# led_kocka_shematic.net
KiCad netlist of a schematic drawn in EAGLE
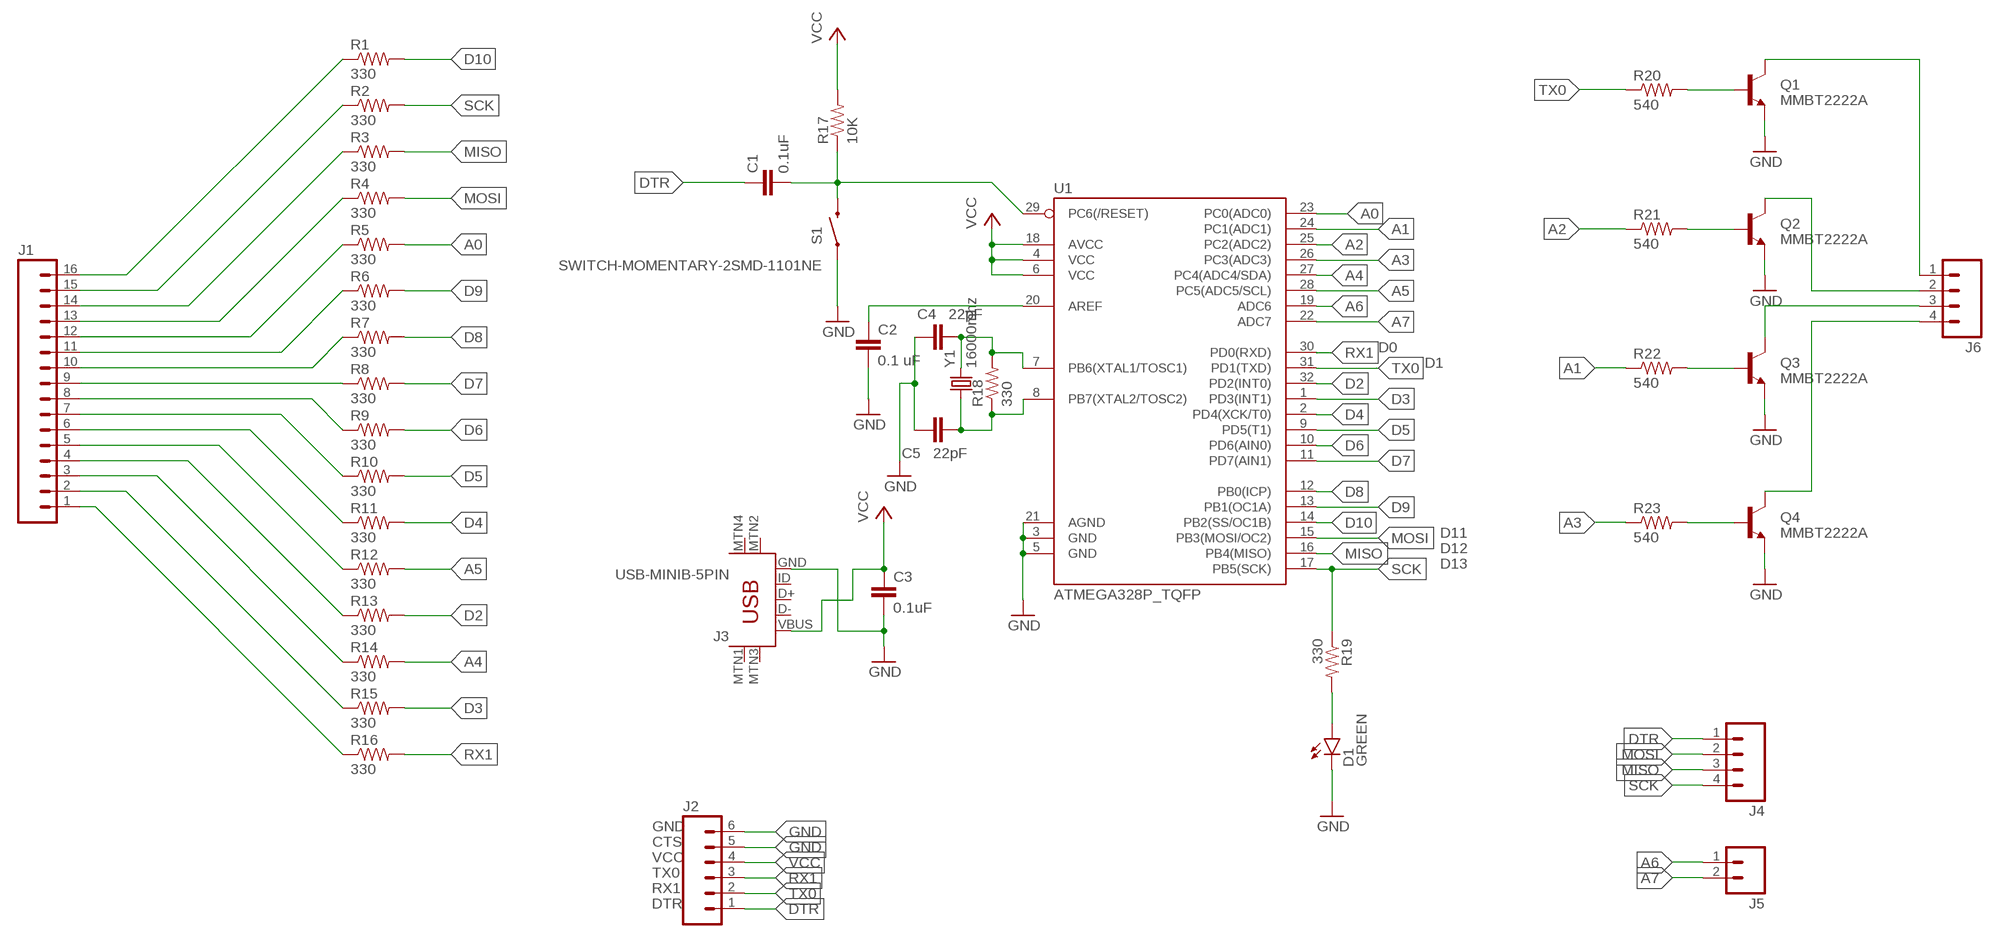
[diagram p0: schematic, sheet 1]

(export (version "E")
  (design (tool "Eeschema 10.0.6"))
  (components
    (comp (ref "C1")
      (value "0.1uF")
      (footprint "eagle-import:0805-CAP")
      (libsource (lib "eagle-import") (part "1UF-25V-10%(0805){dblquote}"))
    )
    (comp (ref "C2")
      (value "0.1 uF")
      (footprint "eagle-import:0805-CAP")
      (libsource (lib "eagle-import") (part "1UF-25V-10%(0805){dblquote}"))
    )
    (comp (ref "C3")
      (value "0.1uF")
      (footprint "eagle-import:0805-CAP")
      (libsource (lib "eagle-import") (part "1UF-25V-10%(0805){dblquote}"))
    )
    (comp (ref "C4")
      (value "22pF")
      (footprint "eagle-import:0805-CAP")
      (libsource (lib "eagle-import") (part "1UF-25V-10%(0805){dblquote}"))
    )
    (comp (ref "C5")
      (value "22pF")
      (footprint "eagle-import:0805-CAP")
      (libsource (lib "eagle-import") (part "1UF-25V-10%(0805){dblquote}"))
    )
    (comp (ref "D1")
      (value "GREEN")
      (footprint "eagle-import:LED-0603")
      (libsource (lib "eagle-import") (part "LED-GREEN0603"))
    )
    (comp (ref "J1")
      (value "M16LONGPADS")
      (footprint "eagle-import:1X16_LONGPADS")
      (libsource (lib "eagle-import") (part "M16LONGPADS"))
    )
    (comp (ref "J2")
      (value "M06LONGPADS")
      (footprint "eagle-import:1X06_LONGPADS")
      (libsource (lib "eagle-import") (part "M06LONGPADS"))
    )
    (comp (ref "J3")
      (value "USB-MINIB-5PIN")
      (footprint "eagle-import:USB-MINIB")
      (libsource (lib "eagle-import") (part "USB-MINIB-5PIN"))
    )
    (comp (ref "J4")
      (value "M04LONGPADS")
      (footprint "eagle-import:1X04_LONGPADS")
      (libsource (lib "eagle-import") (part "M04LONGPADS"))
    )
    (comp (ref "J5")
      (value "M02LOCK_LONGPADS")
      (footprint "eagle-import:1X02_LOCK_LONGPADS")
      (libsource (lib "eagle-import") (part "M02LOCK_LONGPADS"))
    )
    (comp (ref "J6")
      (value "M04LONGPADS")
      (footprint "eagle-import:1X04_LONGPADS")
      (libsource (lib "eagle-import") (part "M04LONGPADS"))
    )
    (comp (ref "Q1")
      (value "MMBT2222A")
      (footprint "eagle-import:SOT23-3")
      (libsource (lib "eagle-import") (part "TRANSISTOR_NPNMMBT2222A"))
    )
    (comp (ref "Q2")
      (value "MMBT2222A")
      (footprint "eagle-import:SOT23-3")
      (libsource (lib "eagle-import") (part "TRANSISTOR_NPNMMBT2222A"))
    )
    (comp (ref "Q3")
      (value "MMBT2222A")
      (footprint "eagle-import:SOT23-3")
      (libsource (lib "eagle-import") (part "TRANSISTOR_NPNMMBT2222A"))
    )
    (comp (ref "Q4")
      (value "MMBT2222A")
      (footprint "eagle-import:SOT23-3")
      (libsource (lib "eagle-import") (part "TRANSISTOR_NPNMMBT2222A"))
    )
    (comp (ref "R1")
      (value "330")
      (footprint "eagle-import:R0805")
      (libsource (lib "eagle-import") (part "R-US_R0805"))
    )
    (comp (ref "R2")
      (value "330")
      (footprint "eagle-import:R0805")
      (libsource (lib "eagle-import") (part "R-US_R0805"))
    )
    (comp (ref "R3")
      (value "330")
      (footprint "eagle-import:R0805")
      (libsource (lib "eagle-import") (part "R-US_R0805"))
    )
    (comp (ref "R4")
      (value "330")
      (footprint "eagle-import:R0805")
      (libsource (lib "eagle-import") (part "R-US_R0805"))
    )
    (comp (ref "R5")
      (value "330")
      (footprint "eagle-import:R0805")
      (libsource (lib "eagle-import") (part "R-US_R0805"))
    )
    (comp (ref "R6")
      (value "330")
      (footprint "eagle-import:R0805")
      (libsource (lib "eagle-import") (part "R-US_R0805"))
    )
    (comp (ref "R7")
      (value "330")
      (footprint "eagle-import:R0805")
      (libsource (lib "eagle-import") (part "R-US_R0805"))
    )
    (comp (ref "R8")
      (value "330")
      (footprint "eagle-import:R0805")
      (libsource (lib "eagle-import") (part "R-US_R0805"))
    )
    (comp (ref "R9")
      (value "330")
      (footprint "eagle-import:R0805")
      (libsource (lib "eagle-import") (part "R-US_R0805"))
    )
    (comp (ref "R10")
      (value "330")
      (footprint "eagle-import:R0805")
      (libsource (lib "eagle-import") (part "R-US_R0805"))
    )
    (comp (ref "R11")
      (value "330")
      (footprint "eagle-import:R0805")
      (libsource (lib "eagle-import") (part "R-US_R0805"))
    )
    (comp (ref "R12")
      (value "330")
      (footprint "eagle-import:R0805")
      (libsource (lib "eagle-import") (part "R-US_R0805"))
    )
    (comp (ref "R13")
      (value "330")
      (footprint "eagle-import:R0805")
      (libsource (lib "eagle-import") (part "R-US_R0805"))
    )
    (comp (ref "R14")
      (value "330")
      (footprint "eagle-import:R0805")
      (libsource (lib "eagle-import") (part "R-US_R0805"))
    )
    (comp (ref "R15")
      (value "330")
      (footprint "eagle-import:R0805")
      (libsource (lib "eagle-import") (part "R-US_R0805"))
    )
    (comp (ref "R16")
      (value "330")
      (footprint "eagle-import:R0805")
      (libsource (lib "eagle-import") (part "R-US_R0805"))
    )
    (comp (ref "R17")
      (value "10K")
      (footprint "eagle-import:R0805")
      (libsource (lib "eagle-import") (part "R-US_R0805"))
    )
    (comp (ref "R18")
      (value "330")
      (footprint "eagle-import:R0805")
      (libsource (lib "eagle-import") (part "R-US_R0805"))
    )
    (comp (ref "R19")
      (value "330")
      (footprint "eagle-import:R0805")
      (libsource (lib "eagle-import") (part "R-US_R0805"))
    )
    (comp (ref "R20")
      (value "540")
      (footprint "eagle-import:R0805")
      (libsource (lib "eagle-import") (part "R-US_R0805"))
    )
    (comp (ref "R21")
      (value "540")
      (footprint "eagle-import:R0805")
      (libsource (lib "eagle-import") (part "R-US_R0805"))
    )
    (comp (ref "R22")
      (value "540")
      (footprint "eagle-import:R0805")
      (libsource (lib "eagle-import") (part "R-US_R0805"))
    )
    (comp (ref "R23")
      (value "540")
      (footprint "eagle-import:R0805")
      (libsource (lib "eagle-import") (part "R-US_R0805"))
    )
    (comp (ref "S1")
      (value "SWITCH-MOMENTARY-2SMD-1101NE")
      (footprint "eagle-import:TACTILE-SWITCH-1101NE")
      (libsource (lib "eagle-import") (part "SWITCH-MOMENTARY-2SMD-1101NE"))
    )
    (comp (ref "U1")
      (value "ATMEGA328P_TQFP")
      (footprint "eagle-import:TQFP32-08")
      (libsource (lib "eagle-import") (part "ATMEGA328P_TQFP"))
    )
    (comp (ref "Y1")
      (value "16000mhz")
      (footprint "eagle-import:HC49UP")
      (libsource (lib "eagle-import") (part "CRYSTALSMD"))
    )
  )
  (nets
    (net (code "1") (name "A0") (class "Default")
      (node (ref "R5") (pin "2") (pinfunction "2_2") (pintype "passive"))
      (node (ref "U1") (pin "23") (pinfunction "PC0(ADC0)_23") (pintype "bidirectional"))
    )
    (net (code "2") (name "A1") (class "Default")
      (node (ref "R22") (pin "1") (pinfunction "1_1") (pintype "passive"))
      (node (ref "U1") (pin "24") (pinfunction "PC1(ADC1)_24") (pintype "bidirectional"))
    )
    (net (code "3") (name "A2") (class "Default")
      (node (ref "R21") (pin "1") (pinfunction "1_1") (pintype "passive"))
      (node (ref "U1") (pin "25") (pinfunction "PC2(ADC2)_25") (pintype "bidirectional"))
    )
    (net (code "4") (name "A3") (class "Default")
      (node (ref "R23") (pin "1") (pinfunction "1_1") (pintype "passive"))
      (node (ref "U1") (pin "26") (pinfunction "PC3(ADC3)_26") (pintype "bidirectional"))
    )
    (net (code "5") (name "A4") (class "Default")
      (node (ref "R14") (pin "2") (pinfunction "2_2") (pintype "passive"))
      (node (ref "U1") (pin "27") (pinfunction "PC4(ADC4/SDA)_27") (pintype "bidirectional"))
    )
    (net (code "6") (name "A5") (class "Default")
      (node (ref "R12") (pin "2") (pinfunction "2_2") (pintype "passive"))
      (node (ref "U1") (pin "28") (pinfunction "PC5(ADC5/SCL)_28") (pintype "bidirectional"))
    )
    (net (code "7") (name "A6") (class "Default")
      (node (ref "J5") (pin "1") (pinfunction "1_1") (pintype "passive"))
      (node (ref "U1") (pin "19") (pinfunction "ADC6_19") (pintype "bidirectional"))
    )
    (net (code "8") (name "A7") (class "Default")
      (node (ref "J5") (pin "2") (pinfunction "2_2") (pintype "passive"))
      (node (ref "U1") (pin "22") (pinfunction "ADC7_22") (pintype "bidirectional"))
    )
    (net (code "9") (name "D2") (class "Default")
      (node (ref "R13") (pin "2") (pinfunction "2_2") (pintype "passive"))
      (node (ref "U1") (pin "32") (pinfunction "PD2(INT0)_32") (pintype "bidirectional"))
    )
    (net (code "10") (name "D3") (class "Default")
      (node (ref "R15") (pin "2") (pinfunction "2_2") (pintype "passive"))
      (node (ref "U1") (pin "1") (pinfunction "PD3(INT1)_1") (pintype "bidirectional"))
    )
    (net (code "11") (name "D4") (class "Default")
      (node (ref "R11") (pin "2") (pinfunction "2_2") (pintype "passive"))
      (node (ref "U1") (pin "2") (pinfunction "PD4(XCK/T0)_2") (pintype "bidirectional"))
    )
    (net (code "12") (name "D5") (class "Default")
      (node (ref "R10") (pin "2") (pinfunction "2_2") (pintype "passive"))
      (node (ref "U1") (pin "9") (pinfunction "PD5(T1)_9") (pintype "bidirectional"))
    )
    (net (code "13") (name "D6") (class "Default")
      (node (ref "R9") (pin "2") (pinfunction "2_2") (pintype "passive"))
      (node (ref "U1") (pin "10") (pinfunction "PD6(AIN0)_10") (pintype "bidirectional"))
    )
    (net (code "14") (name "D7") (class "Default")
      (node (ref "R8") (pin "2") (pinfunction "2_2") (pintype "passive"))
      (node (ref "U1") (pin "11") (pinfunction "PD7(AIN1)_11") (pintype "bidirectional"))
    )
    (net (code "15") (name "D8") (class "Default")
      (node (ref "R7") (pin "2") (pinfunction "2_2") (pintype "passive"))
      (node (ref "U1") (pin "12") (pinfunction "PB0(ICP)_12") (pintype "bidirectional"))
    )
    (net (code "16") (name "D9") (class "Default")
      (node (ref "R6") (pin "2") (pinfunction "2_2") (pintype "passive"))
      (node (ref "U1") (pin "13") (pinfunction "PB1(OC1A)_13") (pintype "bidirectional"))
    )
    (net (code "17") (name "D10") (class "Default")
      (node (ref "R1") (pin "2") (pinfunction "2_2") (pintype "passive"))
      (node (ref "U1") (pin "14") (pinfunction "PB2(SS/OC1B)_14") (pintype "bidirectional"))
    )
    (net (code "18") (name "DTR") (class "Default")
      (node (ref "C1") (pin "1") (pinfunction "1_1") (pintype "passive"))
      (node (ref "J2") (pin "1") (pinfunction "1_1") (pintype "passive"))
      (node (ref "J4") (pin "1") (pinfunction "1_1") (pintype "passive"))
    )
    (net (code "19") (name "GND") (class "Default")
      (node (ref "C2") (pin "2") (pinfunction "2_2") (pintype "passive"))
      (node (ref "C3") (pin "2") (pinfunction "2_2") (pintype "passive"))
      (node (ref "C4") (pin "1") (pinfunction "1_1") (pintype "passive"))
      (node (ref "C5") (pin "1") (pinfunction "1_1") (pintype "passive"))
      (node (ref "D1") (pin "C") (pinfunction "C_C") (pintype "passive"))
      (node (ref "J2") (pin "5") (pinfunction "5_5") (pintype "passive"))
      (node (ref "J2") (pin "6") (pinfunction "6_6") (pintype "passive"))
      (node (ref "J3") (pin "GND") (pinfunction "GND_GND") (pintype "bidirectional"))
      (node (ref "Q1") (pin "2") (pinfunction "E_2") (pintype "passive"))
      (node (ref "Q2") (pin "2") (pinfunction "E_2") (pintype "passive"))
      (node (ref "Q3") (pin "2") (pinfunction "E_2") (pintype "passive"))
      (node (ref "Q4") (pin "2") (pinfunction "E_2") (pintype "passive"))
      (node (ref "S1") (pin "1") (pinfunction "1_1") (pintype "passive"))
      (node (ref "U1") (pin "21") (pinfunction "AGND_21") (pintype "bidirectional"))
      (node (ref "U1") (pin "3") (pinfunction "GND_3") (pintype "bidirectional"))
      (node (ref "U1") (pin "5") (pinfunction "GND_5") (pintype "bidirectional"))
    )
    (net (code "20") (name "MISO") (class "Default")
      (node (ref "J4") (pin "3") (pinfunction "3_3") (pintype "passive"))
      (node (ref "R3") (pin "2") (pinfunction "2_2") (pintype "passive"))
      (node (ref "U1") (pin "16") (pinfunction "PB4(MISO)_16") (pintype "bidirectional"))
    )
    (net (code "21") (name "MOSI") (class "Default")
      (node (ref "J4") (pin "2") (pinfunction "2_2") (pintype "passive"))
      (node (ref "R4") (pin "2") (pinfunction "2_2") (pintype "passive"))
      (node (ref "U1") (pin "15") (pinfunction "PB3(MOSI/OC2)_15") (pintype "bidirectional"))
    )
    (net (code "22") (name "Net-(D1-PadA)") (class "Default")
      (node (ref "D1") (pin "A") (pinfunction "A_A") (pintype "passive"))
      (node (ref "R19") (pin "2") (pinfunction "2_2") (pintype "passive"))
    )
    (net (code "23") (name "Net-(J1-Pad1)") (class "Default")
      (node (ref "J1") (pin "1") (pinfunction "1_1") (pintype "passive"))
      (node (ref "R16") (pin "1") (pinfunction "1_1") (pintype "passive"))
    )
    (net (code "24") (name "Net-(J1-Pad2)") (class "Default")
      (node (ref "J1") (pin "2") (pinfunction "2_2") (pintype "passive"))
      (node (ref "R15") (pin "1") (pinfunction "1_1") (pintype "passive"))
    )
    (net (code "25") (name "Net-(J1-Pad3)") (class "Default")
      (node (ref "J1") (pin "3") (pinfunction "3_3") (pintype "passive"))
      (node (ref "R14") (pin "1") (pinfunction "1_1") (pintype "passive"))
    )
    (net (code "26") (name "Net-(J1-Pad4)") (class "Default")
      (node (ref "J1") (pin "4") (pinfunction "4_4") (pintype "passive"))
      (node (ref "R13") (pin "1") (pinfunction "1_1") (pintype "passive"))
    )
    (net (code "27") (name "Net-(J1-Pad5)") (class "Default")
      (node (ref "J1") (pin "5") (pinfunction "5_5") (pintype "passive"))
      (node (ref "R12") (pin "1") (pinfunction "1_1") (pintype "passive"))
    )
    (net (code "28") (name "Net-(J1-Pad6)") (class "Default")
      (node (ref "J1") (pin "6") (pinfunction "6_6") (pintype "passive"))
      (node (ref "R11") (pin "1") (pinfunction "1_1") (pintype "passive"))
    )
    (net (code "29") (name "Net-(J1-Pad7)") (class "Default")
      (node (ref "J1") (pin "7") (pinfunction "7_7") (pintype "passive"))
      (node (ref "R10") (pin "1") (pinfunction "1_1") (pintype "passive"))
    )
    (net (code "30") (name "Net-(J1-Pad8)") (class "Default")
      (node (ref "J1") (pin "8") (pinfunction "8_8") (pintype "passive"))
      (node (ref "R9") (pin "1") (pinfunction "1_1") (pintype "passive"))
    )
    (net (code "31") (name "Net-(J1-Pad9)") (class "Default")
      (node (ref "J1") (pin "9") (pinfunction "9_9") (pintype "passive"))
      (node (ref "R8") (pin "1") (pinfunction "1_1") (pintype "passive"))
    )
    (net (code "32") (name "Net-(J1-Pad10)") (class "Default")
      (node (ref "J1") (pin "10") (pinfunction "10_10") (pintype "passive"))
      (node (ref "R7") (pin "1") (pinfunction "1_1") (pintype "passive"))
    )
    (net (code "33") (name "Net-(J1-Pad11)") (class "Default")
      (node (ref "J1") (pin "11") (pinfunction "11_11") (pintype "passive"))
      (node (ref "R6") (pin "1") (pinfunction "1_1") (pintype "passive"))
    )
    (net (code "34") (name "Net-(J1-Pad12)") (class "Default")
      (node (ref "J1") (pin "12") (pinfunction "12_12") (pintype "passive"))
      (node (ref "R5") (pin "1") (pinfunction "1_1") (pintype "passive"))
    )
    (net (code "35") (name "Net-(J1-Pad13)") (class "Default")
      (node (ref "J1") (pin "13") (pinfunction "13_13") (pintype "passive"))
      (node (ref "R4") (pin "1") (pinfunction "1_1") (pintype "passive"))
    )
    (net (code "36") (name "Net-(J1-Pad14)") (class "Default")
      (node (ref "J1") (pin "14") (pinfunction "14_14") (pintype "passive"))
      (node (ref "R3") (pin "1") (pinfunction "1_1") (pintype "passive"))
    )
    (net (code "37") (name "Net-(J1-Pad15)") (class "Default")
      (node (ref "J1") (pin "15") (pinfunction "15_15") (pintype "passive"))
      (node (ref "R2") (pin "1") (pinfunction "1_1") (pintype "passive"))
    )
    (net (code "38") (name "Net-(J1-Pad16)") (class "Default")
      (node (ref "J1") (pin "16") (pinfunction "16_16") (pintype "passive"))
      (node (ref "R1") (pin "1") (pinfunction "1_1") (pintype "passive"))
    )
    (net (code "39") (name "Net-(Q1-B)") (class "Default")
      (node (ref "Q1") (pin "1") (pinfunction "B_1") (pintype "passive"))
      (node (ref "R20") (pin "2") (pinfunction "2_2") (pintype "passive"))
    )
    (net (code "40") (name "Net-(Q1-C)") (class "Default")
      (node (ref "J6") (pin "1") (pinfunction "1_1") (pintype "passive"))
      (node (ref "Q1") (pin "3") (pinfunction "C_3") (pintype "passive"))
    )
    (net (code "41") (name "Net-(Q2-B)") (class "Default")
      (node (ref "Q2") (pin "1") (pinfunction "B_1") (pintype "passive"))
      (node (ref "R21") (pin "2") (pinfunction "2_2") (pintype "passive"))
    )
    (net (code "42") (name "Net-(Q2-C)") (class "Default")
      (node (ref "J6") (pin "2") (pinfunction "2_2") (pintype "passive"))
      (node (ref "Q2") (pin "3") (pinfunction "C_3") (pintype "passive"))
    )
    (net (code "43") (name "Net-(Q3-B)") (class "Default")
      (node (ref "Q3") (pin "1") (pinfunction "B_1") (pintype "passive"))
      (node (ref "R22") (pin "2") (pinfunction "2_2") (pintype "passive"))
    )
    (net (code "44") (name "Net-(Q3-C)") (class "Default")
      (node (ref "J6") (pin "3") (pinfunction "3_3") (pintype "passive"))
      (node (ref "Q3") (pin "3") (pinfunction "C_3") (pintype "passive"))
    )
    (net (code "45") (name "Net-(Q4-B)") (class "Default")
      (node (ref "Q4") (pin "1") (pinfunction "B_1") (pintype "passive"))
      (node (ref "R23") (pin "2") (pinfunction "2_2") (pintype "passive"))
    )
    (net (code "46") (name "Net-(Q4-C)") (class "Default")
      (node (ref "J6") (pin "4") (pinfunction "4_4") (pintype "passive"))
      (node (ref "Q4") (pin "3") (pinfunction "C_3") (pintype "passive"))
    )
    (net (code "47") (name "Net-(U1-AREF)") (class "Default")
      (node (ref "C2") (pin "1") (pinfunction "1_1") (pintype "passive"))
      (node (ref "U1") (pin "20") (pinfunction "AREF_20") (pintype "bidirectional"))
    )
    (net (code "48") (name "Net-(U1-PB6(XTAL1{slash}TOSC1))") (class "Default")
      (node (ref "C4") (pin "2") (pinfunction "2_2") (pintype "passive"))
      (node (ref "R18") (pin "2") (pinfunction "2_2") (pintype "passive"))
      (node (ref "U1") (pin "7") (pinfunction "PB6(XTAL1/TOSC1)_7") (pintype "bidirectional"))
      (node (ref "Y1") (pin "2") (pinfunction "2_2") (pintype "passive"))
    )
    (net (code "49") (name "Net-(U1-PB7(XTAL2{slash}TOSC2))") (class "Default")
      (node (ref "C5") (pin "2") (pinfunction "2_2") (pintype "passive"))
      (node (ref "R18") (pin "1") (pinfunction "1_1") (pintype "passive"))
      (node (ref "U1") (pin "8") (pinfunction "PB7(XTAL2/TOSC2)_8") (pintype "bidirectional"))
      (node (ref "Y1") (pin "1") (pinfunction "1_1") (pintype "passive"))
    )
    (net (code "50") (name "Net-(U1-PC6({slash}RESET))") (class "Default")
      (node (ref "C1") (pin "2") (pinfunction "2_2") (pintype "passive"))
      (node (ref "R17") (pin "1") (pinfunction "1_1") (pintype "passive"))
      (node (ref "S1") (pin "2") (pinfunction "2_2") (pintype "passive"))
      (node (ref "U1") (pin "29") (pinfunction "PC6(/RESET)_29") (pintype "bidirectional"))
    )
    (net (code "51") (name "RX1") (class "Default")
      (node (ref "J2") (pin "3") (pinfunction "3_3") (pintype "passive"))
      (node (ref "R16") (pin "2") (pinfunction "2_2") (pintype "passive"))
      (node (ref "U1") (pin "30") (pinfunction "PD0(RXD)_30") (pintype "bidirectional"))
    )
    (net (code "52") (name "SCK") (class "Default")
      (node (ref "J4") (pin "4") (pinfunction "4_4") (pintype "passive"))
      (node (ref "R19") (pin "1") (pinfunction "1_1") (pintype "passive"))
      (node (ref "R2") (pin "2") (pinfunction "2_2") (pintype "passive"))
      (node (ref "U1") (pin "17") (pinfunction "PB5(SCK)_17") (pintype "bidirectional"))
    )
    (net (code "53") (name "TX0") (class "Default")
      (node (ref "J2") (pin "2") (pinfunction "2_2") (pintype "passive"))
      (node (ref "R20") (pin "1") (pinfunction "1_1") (pintype "passive"))
      (node (ref "U1") (pin "31") (pinfunction "PD1(TXD)_31") (pintype "bidirectional"))
    )
    (net (code "54") (name "VCC") (class "Default")
      (node (ref "C3") (pin "1") (pinfunction "1_1") (pintype "passive"))
      (node (ref "J2") (pin "4") (pinfunction "4_4") (pintype "passive"))
      (node (ref "J3") (pin "VBUS") (pinfunction "VBUS_VBUS") (pintype "bidirectional"))
      (node (ref "R17") (pin "2") (pinfunction "2_2") (pintype "passive"))
      (node (ref "U1") (pin "18") (pinfunction "AVCC_18") (pintype "bidirectional"))
      (node (ref "U1") (pin "4") (pinfunction "VCC_4") (pintype "bidirectional"))
      (node (ref "U1") (pin "6") (pinfunction "VCC_6") (pintype "bidirectional"))
    )
    (net (code "55") (name "unconnected-(J3-MTN1-PadMTN3)") (class "Default")
      (node (ref "J3") (pin "MTN3") (pinfunction "MTN1_MTN3") (pintype "bidirectional"))
    )
    (net (code "56") (name "unconnected-(J3-MTN2-PadMTN1)") (class "Default")
      (node (ref "J3") (pin "MTN1") (pinfunction "MTN2_MTN1") (pintype "bidirectional"))
    )
    (net (code "57") (name "unconnected-(J3-MTN3-PadMTN2)") (class "Default")
      (node (ref "J3") (pin "MTN2") (pinfunction "MTN3_MTN2") (pintype "bidirectional"))
    )
    (net (code "58") (name "unconnected-(J3-PadD+)") (class "Default")
      (node (ref "J3") (pin "D+") (pinfunction "D+_D+") (pintype "bidirectional"))
    )
    (net (code "59") (name "unconnected-(J3-PadD-)") (class "Default")
      (node (ref "J3") (pin "D-") (pinfunction "D-_D-") (pintype "bidirectional"))
    )
    (net (code "60") (name "unconnected-(J3-PadID)") (class "Default")
      (node (ref "J3") (pin "ID") (pinfunction "ID_ID") (pintype "bidirectional"))
    )
    (net (code "61") (name "unconnected-(J3-PadMTN4)") (class "Default")
      (node (ref "J3") (pin "MTN4") (pinfunction "MTN4_MTN4") (pintype "bidirectional"))
    )
  )
)
